# 08-multimodal-microcontroller-switches-d.net
KiCad netlist of a schematic drawn in Altium Designer
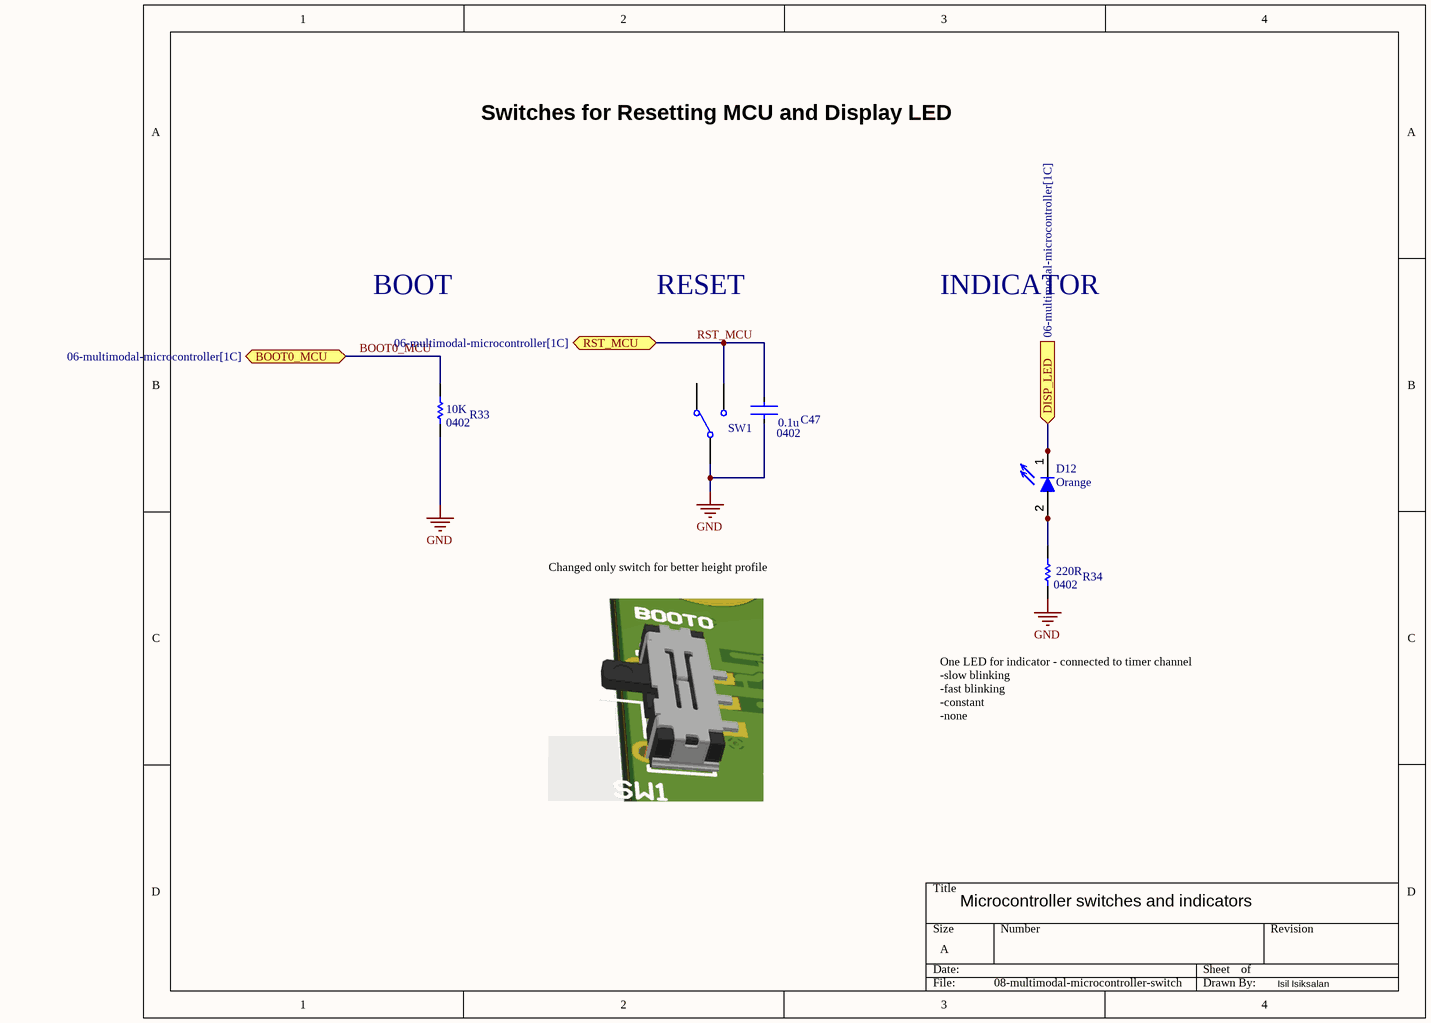
[diagram p0: 08-multimodal-microcontroller-switches-display.SchDoc]

(export (version "E")
  (design (tool "Eeschema 10.0.6"))
  (components
    (comp (ref "C47")
      (value "C1005X7R1H104K050BB")
      (footprint "CAPTDK0402")
      (description "CAP CER 0.1UF 50V X7R 0402")
      (libsource (lib "multimodal") (part "C1005X7R1H104K050BB"))
    )
    (comp (ref "D12")
      (value "Orange")
      (footprint "DISPLAY-LED")
      (description "LED ORANGE CLEAR 0603 SMD")
      (libsource (lib "multimodal") (part "LTST-C191KFKT"))
    )
    (comp (ref "R33")
      (value "RMCF0402FT10K0")
      (footprint "RES-STACK-POLE-0402")
      (description "RES 10K OHM 1% 1/16W 0402")
      (libsource (lib "multimodal") (part "RMCF0402FT10K0"))
    )
    (comp (ref "R34")
      (value "RMCF0402JT220R")
      (footprint "RES-STACK-POLE-0402")
      (description "RES 220 OHM 5% 1/16W 0402")
      (libsource (lib "multimodal") (part "RMCF0402JT220R"))
    )
    (comp (ref "SW1")
      (value "450405020524")
      (footprint "450405020524")
      (description "WS-SLSU SMT Mini Slide Switch Same Side Connection, SPDT, 5VDC, 300mA, 225g")
      (fields (field (name "MANUFACTURER") "Wurth Elektronik"))
      (libsource (lib "multimodal") (part "450405020524"))
    )
  )
  (nets
    (net (code "1") (name "/BOOT0_MCU") (class "Default")
      (node (ref "R33") (pin "2") (pinfunction "2_2") (pintype "passive"))
    )
    (net (code "2") (name "/DISP_LED") (class "Default") (node (ref "D12") (pin "1") (pintype "passive")))
    (net (code "3") (name "/RST_MCU") (class "Default")
      (node (ref "C47") (pin "1") (pinfunction "1_1") (pintype "passive"))
      (node (ref "SW1") (pin "L2") (pinfunction "L2_L2") (pintype "passive"))
    )
    (net (code "4") (name "GND") (class "Default")
      (node (ref "C47") (pin "2") (pinfunction "2_2") (pintype "passive"))
      (node (ref "R33") (pin "1") (pinfunction "1_1") (pintype "passive"))
      (node (ref "R34") (pin "1") (pinfunction "1_1") (pintype "passive"))
      (node (ref "SW1") (pin "COM") (pinfunction "COM_COM") (pintype "passive"))
    )
    (net (code "5") (name "Net-(D12-Pad2)") (class "Default")
      (node (ref "D12") (pin "2") (pintype "passive"))
      (node (ref "R34") (pin "2") (pinfunction "2_2") (pintype "passive"))
    )
    (net (code "6") (name "unconnected-(SW1-PadL1)") (class "Default")
      (node (ref "SW1") (pin "L1") (pinfunction "L1_L1") (pintype "passive"))
    )
  )
)
